# CLK_INPUT.net
KiCad netlist of a schematic drawn in Altium Designer
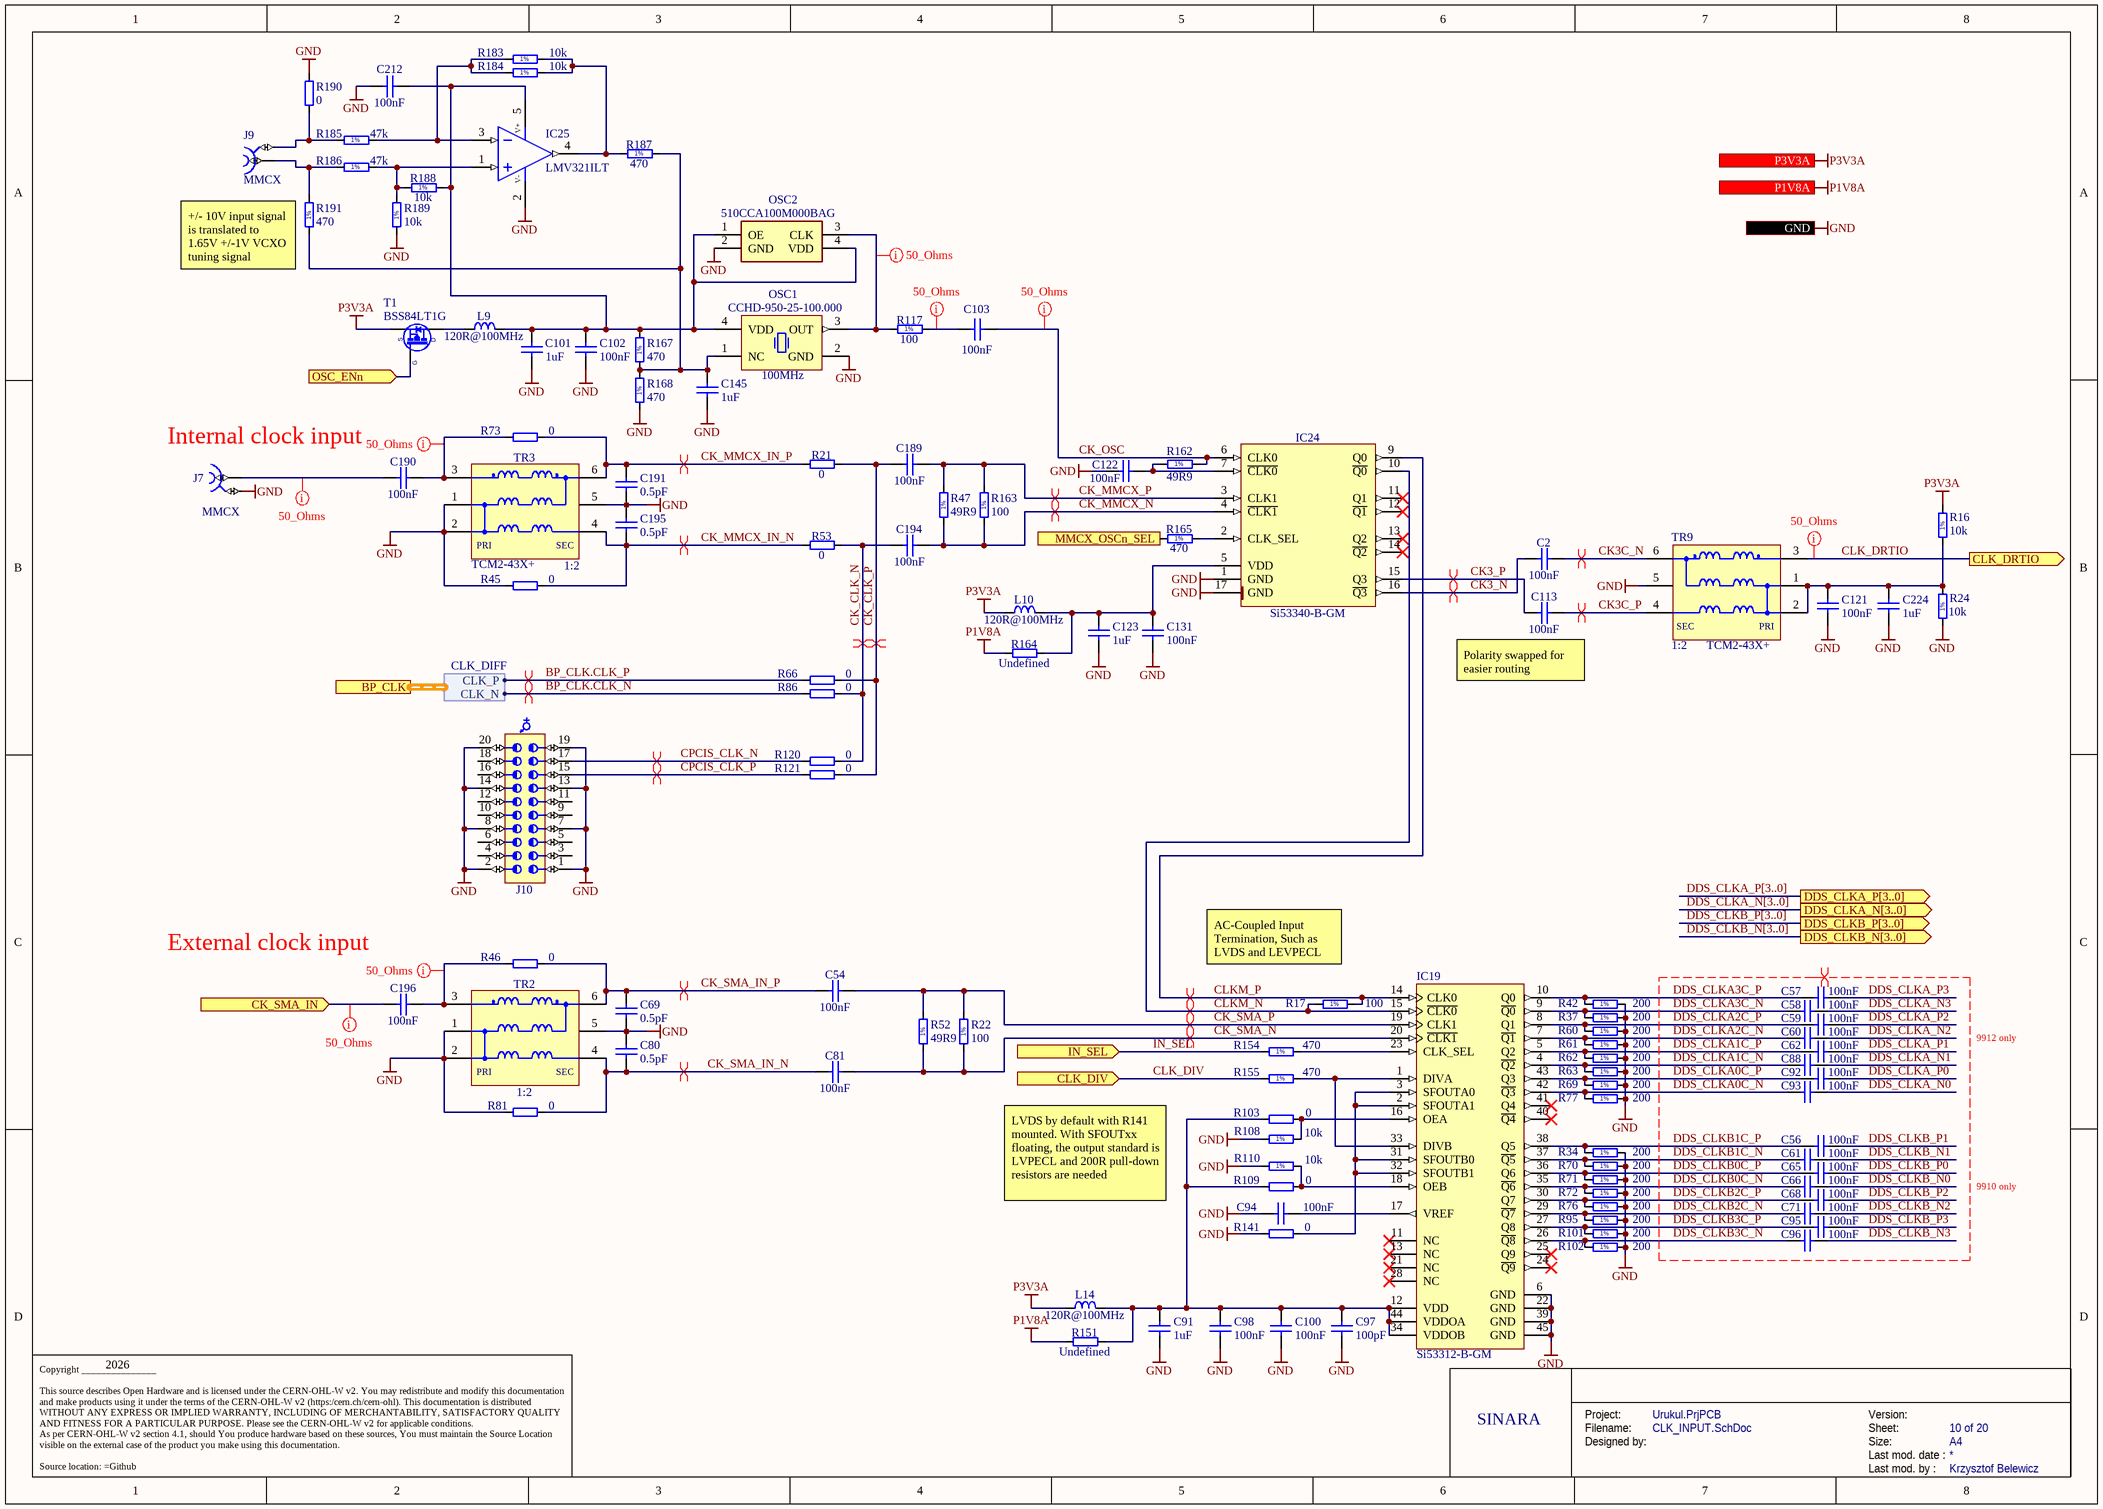
[diagram p0: CLK_INPUT.SchDoc]

(export (version "E")
  (design (tool "Eeschema 10.0.6"))
  (components
    (comp (ref "C2")
      (value "100nF")
      (footprint "CAPC1005X55N")
      (description "Non-polarised capacitor")
      (fields
        (field (name "PART NUMBER") "CC0402_100NF_16V_10%_X5R")
        (field (name "VOLTAGE") "16V")
        (field (name "AUTHOR") "CERN DEM JLC")
      )
      (libsource (lib "Capacitors") (part "Capacitor - non polarized"))
    )
    (comp (ref "C54")
      (value "100nF")
      (footprint "CAPC1005X55N")
      (description "Non-polarised capacitor")
      (fields
        (field (name "PART NUMBER") "CC0402_100NF_16V_10%_X5R")
        (field (name "VOLTAGE") "16V")
        (field (name "AUTHOR") "CERN DEM JLC")
      )
      (libsource (lib "Capacitors") (part "Capacitor - non polarized"))
    )
    (comp (ref "C56")
      (value "100nF")
      (footprint "CAPC1005X55N")
      (description "Non-polarised capacitor")
      (fields
        (field (name "PART NUMBER") "CC0402_100NF_16V_10%_X5R")
        (field (name "VOLTAGE") "16V")
        (field (name "AUTHOR") "CERN DEM JLC")
      )
      (libsource (lib "Capacitors") (part "Capacitor - non polarized"))
    )
    (comp (ref "C57")
      (value "100nF")
      (footprint "CAPC1005X55N")
      (description "Non-polarised capacitor")
      (fields
        (field (name "PART NUMBER") "CC0402_100NF_16V_10%_X5R")
        (field (name "VOLTAGE") "16V")
        (field (name "AUTHOR") "CERN DEM JLC")
      )
      (libsource (lib "Capacitors") (part "Capacitor - non polarized"))
    )
    (comp (ref "C58")
      (value "100nF")
      (footprint "CAPC1005X55N")
      (description "Non-polarised capacitor")
      (fields
        (field (name "PART NUMBER") "CC0402_100NF_16V_10%_X5R")
        (field (name "VOLTAGE") "16V")
        (field (name "AUTHOR") "CERN DEM JLC")
      )
      (libsource (lib "Capacitors") (part "Capacitor - non polarized"))
    )
    (comp (ref "C59")
      (value "100nF")
      (footprint "CAPC1005X55N")
      (description "Non-polarised capacitor")
      (fields
        (field (name "PART NUMBER") "CC0402_100NF_16V_10%_X5R")
        (field (name "VOLTAGE") "16V")
        (field (name "AUTHOR") "CERN DEM JLC")
      )
      (libsource (lib "Capacitors") (part "Capacitor - non polarized"))
    )
    (comp (ref "C60")
      (value "100nF")
      (footprint "CAPC1005X55N")
      (description "Non-polarised capacitor")
      (fields
        (field (name "PART NUMBER") "CC0402_100NF_16V_10%_X5R")
        (field (name "VOLTAGE") "16V")
        (field (name "AUTHOR") "CERN DEM JLC")
      )
      (libsource (lib "Capacitors") (part "Capacitor - non polarized"))
    )
    (comp (ref "C61")
      (value "100nF")
      (footprint "CAPC1005X55N")
      (description "Non-polarised capacitor")
      (fields
        (field (name "PART NUMBER") "CC0402_100NF_16V_10%_X5R")
        (field (name "VOLTAGE") "16V")
        (field (name "AUTHOR") "CERN DEM JLC")
      )
      (libsource (lib "Capacitors") (part "Capacitor - non polarized"))
    )
    (comp (ref "C62")
      (value "100nF")
      (footprint "CAPC1005X55N")
      (description "Non-polarised capacitor")
      (fields
        (field (name "PART NUMBER") "CC0402_100NF_16V_10%_X5R")
        (field (name "VOLTAGE") "16V")
        (field (name "AUTHOR") "CERN DEM JLC")
      )
      (libsource (lib "Capacitors") (part "Capacitor - non polarized"))
    )
    (comp (ref "C65")
      (value "100nF")
      (footprint "CAPC1005X55N")
      (description "Non-polarised capacitor")
      (fields
        (field (name "PART NUMBER") "CC0402_100NF_16V_10%_X5R")
        (field (name "VOLTAGE") "16V")
        (field (name "AUTHOR") "CERN DEM JLC")
      )
      (libsource (lib "Capacitors") (part "Capacitor - non polarized"))
    )
    (comp (ref "C66")
      (value "100nF")
      (footprint "CAPC1005X55N")
      (description "Non-polarised capacitor")
      (fields
        (field (name "PART NUMBER") "CC0402_100NF_16V_10%_X5R")
        (field (name "VOLTAGE") "16V")
        (field (name "AUTHOR") "CERN DEM JLC")
      )
      (libsource (lib "Capacitors") (part "Capacitor - non polarized"))
    )
    (comp (ref "C68")
      (value "100nF")
      (footprint "CAPC1005X55N")
      (description "Non-polarised capacitor")
      (fields
        (field (name "PART NUMBER") "CC0402_100NF_16V_10%_X5R")
        (field (name "VOLTAGE") "16V")
        (field (name "AUTHOR") "CERN DEM JLC")
      )
      (libsource (lib "Capacitors") (part "Capacitor - non polarized"))
    )
    (comp (ref "C69")
      (value "0.5pF")
      (footprint "CAPC1005X50N")
      (description "Non-polarised capacitor")
      (fields
        (field (name "PART NUMBER") "CC0402_0.5PF_25V_0.05PF_AVX_04023J0R5ABSTR")
        (field (name "VOLTAGE") "25V")
        (field (name "AUTHOR") "CERN DEM JLC")
      )
      (libsource (lib "Capacitors") (part "Capacitor - non polarized"))
    )
    (comp (ref "C71")
      (value "100nF")
      (footprint "CAPC1005X55N")
      (description "Non-polarised capacitor")
      (fields
        (field (name "PART NUMBER") "CC0402_100NF_16V_10%_X5R")
        (field (name "VOLTAGE") "16V")
        (field (name "AUTHOR") "CERN DEM JLC")
      )
      (libsource (lib "Capacitors") (part "Capacitor - non polarized"))
    )
    (comp (ref "C80")
      (value "0.5pF")
      (footprint "CAPC1005X50N")
      (description "Non-polarised capacitor")
      (fields
        (field (name "PART NUMBER") "CC0402_0.5PF_25V_0.05PF_AVX_04023J0R5ABSTR")
        (field (name "VOLTAGE") "25V")
        (field (name "AUTHOR") "CERN DEM JLC")
      )
      (libsource (lib "Capacitors") (part "Capacitor - non polarized"))
    )
    (comp (ref "C81")
      (value "100nF")
      (footprint "CAPC1005X55N")
      (description "Non-polarised capacitor")
      (fields
        (field (name "PART NUMBER") "CC0402_100NF_16V_10%_X5R")
        (field (name "VOLTAGE") "16V")
        (field (name "AUTHOR") "CERN DEM JLC")
      )
      (libsource (lib "Capacitors") (part "Capacitor - non polarized"))
    )
    (comp (ref "C88")
      (value "100nF")
      (footprint "CAPC1005X55N")
      (description "Non-polarised capacitor")
      (fields
        (field (name "PART NUMBER") "CC0402_100NF_16V_10%_X5R")
        (field (name "VOLTAGE") "16V")
        (field (name "AUTHOR") "CERN DEM JLC")
      )
      (libsource (lib "Capacitors") (part "Capacitor - non polarized"))
    )
    (comp (ref "C91")
      (value "1uF")
      (footprint "CAPC1005X55N")
      (description "Non-polarised capacitor")
      (fields
        (field (name "PART NUMBER") "CC0402_1UF_16V_10%_X5R")
        (field (name "VOLTAGE") "16V")
        (field (name "AUTHOR") "CERN DEM JLC")
      )
      (libsource (lib "Capacitors") (part "Capacitor - non polarized"))
    )
    (comp (ref "C92")
      (value "100nF")
      (footprint "CAPC1005X55N")
      (description "Non-polarised capacitor")
      (fields
        (field (name "PART NUMBER") "CC0402_100NF_16V_10%_X5R")
        (field (name "VOLTAGE") "16V")
        (field (name "AUTHOR") "CERN DEM JLC")
      )
      (libsource (lib "Capacitors") (part "Capacitor - non polarized"))
    )
    (comp (ref "C93")
      (value "100nF")
      (footprint "CAPC1005X55N")
      (description "Non-polarised capacitor")
      (fields
        (field (name "PART NUMBER") "CC0402_100NF_16V_10%_X5R")
        (field (name "VOLTAGE") "16V")
        (field (name "AUTHOR") "CERN DEM JLC")
      )
      (libsource (lib "Capacitors") (part "Capacitor - non polarized"))
    )
    (comp (ref "C94")
      (value "100nF")
      (footprint "CAPC1005X55N")
      (description "Non-polarised capacitor")
      (fields
        (field (name "PART NUMBER") "CC0402_100NF_16V_10%_X5R")
        (field (name "VOLTAGE") "16V")
        (field (name "AUTHOR") "CERN DEM JLC")
      )
      (libsource (lib "Capacitors") (part "Capacitor - non polarized"))
    )
    (comp (ref "C95")
      (value "100nF")
      (footprint "CAPC1005X55N")
      (description "Non-polarised capacitor")
      (fields
        (field (name "PART NUMBER") "CC0402_100NF_16V_10%_X5R")
        (field (name "VOLTAGE") "16V")
        (field (name "AUTHOR") "CERN DEM JLC")
      )
      (libsource (lib "Capacitors") (part "Capacitor - non polarized"))
    )
    (comp (ref "C96")
      (value "100nF")
      (footprint "CAPC1005X55N")
      (description "Non-polarised capacitor")
      (fields
        (field (name "PART NUMBER") "CC0402_100NF_16V_10%_X5R")
        (field (name "VOLTAGE") "16V")
        (field (name "AUTHOR") "CERN DEM JLC")
      )
      (libsource (lib "Capacitors") (part "Capacitor - non polarized"))
    )
    (comp (ref "C97")
      (value "100pF")
      (footprint "CAPC1005X55N")
      (description "Non-polarised capacitor")
      (fields
        (field (name "PART NUMBER") "CC0402_100PF_50V_5%_C0G")
        (field (name "VOLTAGE") "50V")
        (field (name "AUTHOR") "CERN DEM JLC")
      )
      (libsource (lib "Capacitors") (part "Capacitor - non polarized"))
    )
    (comp (ref "C98")
      (value "100nF")
      (footprint "CAPC1005X55N")
      (description "Non-polarised capacitor")
      (fields
        (field (name "PART NUMBER") "CC0402_100NF_16V_10%_X5R")
        (field (name "VOLTAGE") "16V")
        (field (name "AUTHOR") "CERN DEM JLC")
      )
      (libsource (lib "Capacitors") (part "Capacitor - non polarized"))
    )
    (comp (ref "C100")
      (value "100nF")
      (footprint "CAPC1005X55N")
      (description "Non-polarised capacitor")
      (fields
        (field (name "PART NUMBER") "CC0402_100NF_16V_10%_X5R")
        (field (name "VOLTAGE") "16V")
        (field (name "AUTHOR") "CERN DEM JLC")
      )
      (libsource (lib "Capacitors") (part "Capacitor - non polarized"))
    )
    (comp (ref "C101")
      (value "1uF")
      (footprint "CAPC1005X55N")
      (description "Non-polarised capacitor")
      (fields
        (field (name "PART NUMBER") "CC0402_1UF_16V_10%_X5R")
        (field (name "VOLTAGE") "16V")
        (field (name "AUTHOR") "CERN DEM JLC")
      )
      (libsource (lib "Capacitors") (part "Capacitor - non polarized"))
    )
    (comp (ref "C102")
      (value "100nF")
      (footprint "CAPC1005X55N")
      (description "Non-polarised capacitor")
      (fields
        (field (name "PART NUMBER") "CC0402_100NF_16V_10%_X5R")
        (field (name "VOLTAGE") "16V")
        (field (name "AUTHOR") "CERN DEM JLC")
      )
      (libsource (lib "Capacitors") (part "Capacitor - non polarized"))
    )
    (comp (ref "C103")
      (value "100nF")
      (footprint "CAPC1005X55N")
      (description "Non-polarised capacitor")
      (fields
        (field (name "PART NUMBER") "CC0402_100NF_16V_10%_X5R")
        (field (name "VOLTAGE") "16V")
        (field (name "AUTHOR") "CERN DEM JLC")
      )
      (libsource (lib "Capacitors") (part "Capacitor - non polarized"))
    )
    (comp (ref "C113")
      (value "100nF")
      (footprint "CAPC1005X55N")
      (description "Non-polarised capacitor")
      (fields
        (field (name "PART NUMBER") "CC0402_100NF_16V_10%_X5R")
        (field (name "VOLTAGE") "16V")
        (field (name "AUTHOR") "CERN DEM JLC")
      )
      (libsource (lib "Capacitors") (part "Capacitor - non polarized"))
    )
    (comp (ref "C121")
      (value "100nF")
      (footprint "CAPC1005X55N")
      (description "Non-polarised capacitor")
      (fields
        (field (name "PART NUMBER") "CC0402_100NF_16V_10%_X5R")
        (field (name "VOLTAGE") "16V")
        (field (name "AUTHOR") "CERN DEM JLC")
      )
      (libsource (lib "Capacitors") (part "Capacitor - non polarized"))
    )
    (comp (ref "C122")
      (value "100nF")
      (footprint "CAPC1005X55N")
      (description "Non-polarised capacitor")
      (fields
        (field (name "PART NUMBER") "CC0402_100NF_16V_10%_X5R")
        (field (name "VOLTAGE") "16V")
        (field (name "AUTHOR") "CERN DEM JLC")
      )
      (libsource (lib "Capacitors") (part "Capacitor - non polarized"))
    )
    (comp (ref "C123")
      (value "1uF")
      (footprint "CAPC1005X55N")
      (description "Non-polarised capacitor")
      (fields
        (field (name "PART NUMBER") "CC0402_1UF_16V_10%_X5R")
        (field (name "VOLTAGE") "16V")
        (field (name "AUTHOR") "CERN DEM JLC")
      )
      (libsource (lib "Capacitors") (part "Capacitor - non polarized"))
    )
    (comp (ref "C131")
      (value "100nF")
      (footprint "CAPC1005X55N")
      (description "Non-polarised capacitor")
      (fields
        (field (name "PART NUMBER") "CC0402_100NF_16V_10%_X5R")
        (field (name "VOLTAGE") "16V")
        (field (name "AUTHOR") "CERN DEM JLC")
      )
      (libsource (lib "Capacitors") (part "Capacitor - non polarized"))
    )
    (comp (ref "C145")
      (value "1uF")
      (footprint "CAPC1005X55N")
      (description "Non-polarised capacitor")
      (fields
        (field (name "PART NUMBER") "CC0402_1UF_16V_10%_X5R")
        (field (name "VOLTAGE") "16V")
        (field (name "AUTHOR") "CERN DEM JLC")
      )
      (libsource (lib "Capacitors") (part "Capacitor - non polarized"))
    )
    (comp (ref "C189")
      (value "100nF")
      (footprint "CAPC1005X55N")
      (description "Non-polarised capacitor")
      (fields
        (field (name "PART NUMBER") "CC0402_100NF_16V_10%_X5R")
        (field (name "VOLTAGE") "16V")
        (field (name "AUTHOR") "CERN DEM JLC")
      )
      (libsource (lib "Capacitors") (part "Capacitor - non polarized"))
    )
    (comp (ref "C190")
      (value "100nF")
      (footprint "CAPC1005X55N")
      (description "Non-polarised capacitor")
      (fields
        (field (name "PART NUMBER") "CC0402_100NF_16V_10%_X5R")
        (field (name "VOLTAGE") "16V")
        (field (name "AUTHOR") "CERN DEM JLC")
      )
      (libsource (lib "Capacitors") (part "Capacitor - non polarized"))
    )
    (comp (ref "C191")
      (value "0.5pF")
      (footprint "CAPC1005X50N")
      (description "Non-polarised capacitor")
      (fields
        (field (name "PART NUMBER") "CC0402_0.5PF_25V_0.05PF_AVX_04023J0R5ABSTR")
        (field (name "VOLTAGE") "25V")
        (field (name "AUTHOR") "CERN DEM JLC")
      )
      (libsource (lib "Capacitors") (part "Capacitor - non polarized"))
    )
    (comp (ref "C194")
      (value "100nF")
      (footprint "CAPC1005X55N")
      (description "Non-polarised capacitor")
      (fields
        (field (name "PART NUMBER") "CC0402_100NF_16V_10%_X5R")
        (field (name "VOLTAGE") "16V")
        (field (name "AUTHOR") "CERN DEM JLC")
      )
      (libsource (lib "Capacitors") (part "Capacitor - non polarized"))
    )
    (comp (ref "C195")
      (value "0.5pF")
      (footprint "CAPC1005X50N")
      (description "Non-polarised capacitor")
      (fields
        (field (name "PART NUMBER") "CC0402_0.5PF_25V_0.05PF_AVX_04023J0R5ABSTR")
        (field (name "VOLTAGE") "25V")
        (field (name "AUTHOR") "CERN DEM JLC")
      )
      (libsource (lib "Capacitors") (part "Capacitor - non polarized"))
    )
    (comp (ref "C196")
      (value "100nF")
      (footprint "CAPC1005X55N")
      (description "Non-polarised capacitor")
      (fields
        (field (name "PART NUMBER") "CC0402_100NF_16V_10%_X5R")
        (field (name "VOLTAGE") "16V")
        (field (name "AUTHOR") "CERN DEM JLC")
      )
      (libsource (lib "Capacitors") (part "Capacitor - non polarized"))
    )
    (comp (ref "C212")
      (value "100nF")
      (footprint "CAPC1005X55N")
      (description "Non-polarised capacitor")
      (fields
        (field (name "PART NUMBER") "CC0402_100NF_16V_10%_X5R")
        (field (name "VOLTAGE") "16V")
        (field (name "AUTHOR") "CERN DEM JLC")
      )
      (libsource (lib "Capacitors") (part "Capacitor - non polarized"))
    )
    (comp (ref "C224")
      (value "1uF")
      (footprint "CAPC1005X55N")
      (description "Non-polarised capacitor")
      (fields
        (field (name "PART NUMBER") "CC0402_1UF_16V_10%_X5R")
        (field (name "VOLTAGE") "16V")
        (field (name "AUTHOR") "CERN DEM JLC")
      )
      (libsource (lib "Capacitors") (part "Capacitor - non polarized"))
    )
    (comp (ref "IC19")
      (value "Si53312-B-GM")
      (footprint "SLAB-QFN-44-2800x2800TP_N")
      (fields (field (name "MANUFACTURER") "Silicon Labs"))
      (libsource (lib "Altium Content Vault") (part "SLAB-Si53312-QFN-44-45"))
    )
    (comp (ref "IC24")
      (value "Si53340-B-GM")
      (footprint "QFN50P300X300X90-17N-S175")
      (description "Low-Jitter LVDS Fanout Clock Buffers, 10-Output,  Any-Input, Any-Frequency up to 1250MHz")
      (fields (field (name "MANUFACTURER") "SILICON LABS") (field (name "AUTHOR") "CERN DEM MR"))
      (libsource (lib "ICs And Semiconductors") (part "Si53340"))
    )
    (comp (ref "IC25")
      (value "LMV321ILT")
      (footprint "SOT95P280X145-5N")
      (description "Operational Amplifier")
      (fields (field (name "MANUFACTURER") "ST MICROELECTRONICS") (field (name "AUTHOR") "CERN DEM MR"))
      (libsource (lib "ICs And Semiconductors") (part "Operational Amplifier Type10"))
    )
    (comp (ref "J7")
      (value "MMCX")
      (footprint "SAMTEC_MMCX-J-P-H-ST-TH1")
      (fields
        (field (name "PART NUMBER") "SAMTEC_MMCX-J-P-H-ST-TH1")
        (field (name "MANUFACTURER") "SAMTEC")
        (field (name "MANUFACTURER PART NUMBER") "MMCX-J-P-H-ST-TH1")
        (field (name "AUTHOR") "CERN DEM JLC")
      )
      (libsource (lib "Connectors") (part "Coax_1Female_1Shield"))
    )
    (comp (ref "J9")
      (value "MMCX")
      (footprint "SAMTEC_MMCX-J-P-H-ST-TH1")
      (fields
        (field (name "PART NUMBER") "SAMTEC_MMCX-J-P-H-ST-TH1")
        (field (name "MANUFACTURER") "SAMTEC")
        (field (name "MANUFACTURER PART NUMBER") "MMCX-J-P-H-ST-TH1")
        (field (name "AUTHOR") "CERN DEM JLC")
      )
      (libsource (lib "") (part "Coax_1Female_1Shield_1"))
    )
    (comp (ref "J10")
      (value "~")
      (footprint "SAMTEC_LSS-110-01-L-DV-A")
      (description "Connector 20 Hermaphroditic")
      (fields
        (field (name "PART NUMBER") "SAMTEC_LSS-110-01-L-DV-A")
        (field (name "MANUFACTURER") "SAMTEC")
        (field (name "AUTHOR") "CERN DEM MR")
      )
      (libsource (lib "Connectors") (part "Connector 20 Hermaphroditic"))
    )
    (comp (ref "L9")
      (value "120R@100MHz")
      (footprint "INDC1608X95N")
      (description "Inductor")
      (fields
        (field (name "PART NUMBER") "IND0603_MURATA_BLM18PG121SN1D")
        (field (name "POWER") "2A")
        (field (name "AUTHOR") "CERN DEM BC")
      )
      (libsource (lib "Inductors & Transformers") (part "Inductor"))
    )
    (comp (ref "L10")
      (value "120R@100MHz")
      (footprint "INDC1608X95N")
      (description "Inductor")
      (fields
        (field (name "PART NUMBER") "IND0603_MURATA_BLM18PG121SN1D")
        (field (name "POWER") "2A")
        (field (name "AUTHOR") "CERN DEM BC")
      )
      (libsource (lib "Inductors & Transformers") (part "Inductor"))
    )
    (comp (ref "L14")
      (value "120R@100MHz")
      (footprint "INDC1608X95N")
      (description "Inductor")
      (fields
        (field (name "PART NUMBER") "IND0603_MURATA_BLM18PG121SN1D")
        (field (name "POWER") "2A")
        (field (name "AUTHOR") "CERN DEM BC")
      )
      (libsource (lib "Inductors & Transformers") (part "Inductor"))
    )
    (comp (ref "OSC1")
      (value "100MHz")
      (footprint "OSC_CRYSTEK_CCHD-950")
      (description "100MHz low noise oscillator")
      (fields
        (field (name "PART NUMBER") "OSC_100MHZ_CRYSTEK_CCHD-950-25-100.000")
        (field (name "MANUFACTURER") "CRYSTEK CRYSTAL")
        (field (name "MANUFACTURER PART NUMBER") "CCHD-950-25-100.000")
        (field (name "AUTHOR") "GK")
      )
      (libsource (lib "LIBRARY_SCH") (part "OSC_CCHD-950"))
    )
    (comp (ref "OSC2")
      (value "510CCA100M000BAG")
      (footprint "SamacSys:510CBA49M1520BAG")
      (description "Crystal or Oscillator")
      (fields (field (name "MOUSER PART NUMBER") "634-510CCA100M000BAG"))
      (libsource (lib "*") (part "510CCA100M000BAG"))
    )
    (comp (ref "R16")
      (value "10k")
      (footprint "RESC1005X40N")
      (description "Resistor - 1%")
      (fields
        (field (name "PART NUMBER") "R0402_10K_1%_0.0625W_100PPM")
        (field (name "POWER") "0.0625W")
        (field (name "AUTHOR") "CERN DEM JLC")
      )
      (libsource (lib "Resistors") (part "Resistor - 1%"))
    )
    (comp (ref "R17")
      (value "100")
      (footprint "RESC1005X40N")
      (description "Resistor - 1%")
      (fields
        (field (name "PART NUMBER") "R0402_100R_1%_0.0625W_100PPM")
        (field (name "POWER") "0.0625W")
        (field (name "AUTHOR") "CERN DEM JLC")
      )
      (libsource (lib "Resistors") (part "Resistor - 1%"))
    )
    (comp (ref "R21")
      (value "0")
      (footprint "RESC1005X40N")
      (description "Resistor")
      (fields
        (field (name "PART NUMBER") "R0402_0R_JUMPER")
        (field (name "MANUFACTURER") "GENERIC")
        (field (name "AUTHOR") "CERN DEM JLC")
      )
      (libsource (lib "Resistors") (part "Resistor"))
    )
    (comp (ref "R22")
      (value "100")
      (footprint "RESC1005X40N")
      (description "Resistor - 1%")
      (fields
        (field (name "PART NUMBER") "R0402_100R_1%_0.0625W_100PPM")
        (field (name "POWER") "0.0625W")
        (field (name "AUTHOR") "CERN DEM JLC")
      )
      (libsource (lib "Resistors") (part "Resistor - 1%"))
    )
    (comp (ref "R24")
      (value "10k")
      (footprint "RESC1005X40N")
      (description "Resistor - 1%")
      (fields
        (field (name "PART NUMBER") "R0402_10K_1%_0.0625W_100PPM")
        (field (name "POWER") "0.0625W")
        (field (name "AUTHOR") "CERN DEM JLC")
      )
      (libsource (lib "Resistors") (part "Resistor - 1%"))
    )
    (comp (ref "R34")
      (value "200")
      (footprint "RESC1005X40N")
      (description "Resistor - 1%")
      (fields
        (field (name "PART NUMBER") "R0402_200R_1%_0.0625W_100PPM")
        (field (name "POWER") "0.0625W")
        (field (name "AUTHOR") "CERN DEM JLC")
      )
      (libsource (lib "Resistors") (part "Resistor - 1%"))
    )
    (comp (ref "R37")
      (value "200")
      (footprint "RESC1005X40N")
      (description "Resistor - 1%")
      (fields
        (field (name "PART NUMBER") "R0402_200R_1%_0.0625W_100PPM")
        (field (name "POWER") "0.0625W")
        (field (name "AUTHOR") "CERN DEM JLC")
      )
      (libsource (lib "Resistors") (part "Resistor - 1%"))
    )
    (comp (ref "R42")
      (value "200")
      (footprint "RESC1005X40N")
      (description "Resistor - 1%")
      (fields
        (field (name "PART NUMBER") "R0402_200R_1%_0.0625W_100PPM")
        (field (name "POWER") "0.0625W")
        (field (name "AUTHOR") "CERN DEM JLC")
      )
      (libsource (lib "Resistors") (part "Resistor - 1%"))
    )
    (comp (ref "R45")
      (value "0")
      (footprint "RESC1005X40N")
      (description "Resistor")
      (fields
        (field (name "PART NUMBER") "R0402_0R_JUMPER")
        (field (name "MANUFACTURER") "GENERIC")
        (field (name "AUTHOR") "CERN DEM JLC")
      )
      (libsource (lib "Resistors") (part "Resistor"))
    )
    (comp (ref "R46")
      (value "0")
      (footprint "RESC1005X40N")
      (description "Resistor")
      (fields
        (field (name "PART NUMBER") "R0402_0R_JUMPER")
        (field (name "MANUFACTURER") "GENERIC")
        (field (name "AUTHOR") "CERN DEM JLC")
      )
      (libsource (lib "Resistors") (part "Resistor"))
    )
    (comp (ref "R47")
      (value "49R9")
      (footprint "RESC1005X40N")
      (description "Resistor - 1%")
      (fields
        (field (name "PART NUMBER") "R0402_49R9_1%_0.0625W_100PPM")
        (field (name "POWER") "0.0625W")
        (field (name "AUTHOR") "CERN DEM JLC")
      )
      (libsource (lib "Resistors") (part "Resistor - 1%"))
    )
    (comp (ref "R52")
      (value "49R9")
      (footprint "RESC1005X40N")
      (description "Resistor - 1%")
      (fields
        (field (name "PART NUMBER") "R0402_49R9_1%_0.0625W_100PPM")
        (field (name "POWER") "0.0625W")
        (field (name "AUTHOR") "CERN DEM JLC")
      )
      (libsource (lib "Resistors") (part "Resistor - 1%"))
    )
    (comp (ref "R53")
      (value "0")
      (footprint "RESC1005X40N")
      (description "Resistor")
      (fields
        (field (name "PART NUMBER") "R0402_0R_JUMPER")
        (field (name "MANUFACTURER") "GENERIC")
        (field (name "AUTHOR") "CERN DEM JLC")
      )
      (libsource (lib "Resistors") (part "Resistor"))
    )
    (comp (ref "R60")
      (value "200")
      (footprint "RESC1005X40N")
      (description "Resistor - 1%")
      (fields
        (field (name "PART NUMBER") "R0402_200R_1%_0.0625W_100PPM")
        (field (name "POWER") "0.0625W")
        (field (name "AUTHOR") "CERN DEM JLC")
      )
      (libsource (lib "Resistors") (part "Resistor - 1%"))
    )
    (comp (ref "R61")
      (value "200")
      (footprint "RESC1005X40N")
      (description "Resistor - 1%")
      (fields
        (field (name "PART NUMBER") "R0402_200R_1%_0.0625W_100PPM")
        (field (name "POWER") "0.0625W")
        (field (name "AUTHOR") "CERN DEM JLC")
      )
      (libsource (lib "Resistors") (part "Resistor - 1%"))
    )
    (comp (ref "R62")
      (value "200")
      (footprint "RESC1005X40N")
      (description "Resistor - 1%")
      (fields
        (field (name "PART NUMBER") "R0402_200R_1%_0.0625W_100PPM")
        (field (name "POWER") "0.0625W")
        (field (name "AUTHOR") "CERN DEM JLC")
      )
      (libsource (lib "Resistors") (part "Resistor - 1%"))
    )
    (comp (ref "R63")
      (value "200")
      (footprint "RESC1005X40N")
      (description "Resistor - 1%")
      (fields
        (field (name "PART NUMBER") "R0402_200R_1%_0.0625W_100PPM")
        (field (name "POWER") "0.0625W")
        (field (name "AUTHOR") "CERN DEM JLC")
      )
      (libsource (lib "Resistors") (part "Resistor - 1%"))
    )
    (comp (ref "R66")
      (value "0")
      (footprint "RESC1005X40N")
      (description "Resistor")
      (fields
        (field (name "PART NUMBER") "R0402_0R_JUMPER")
        (field (name "MANUFACTURER") "GENERIC")
        (field (name "AUTHOR") "CERN DEM JLC")
      )
      (libsource (lib "Resistors") (part "Resistor"))
    )
    (comp (ref "R69")
      (value "200")
      (footprint "RESC1005X40N")
      (description "Resistor - 1%")
      (fields
        (field (name "PART NUMBER") "R0402_200R_1%_0.0625W_100PPM")
        (field (name "POWER") "0.0625W")
        (field (name "AUTHOR") "CERN DEM JLC")
      )
      (libsource (lib "Resistors") (part "Resistor - 1%"))
    )
    (comp (ref "R70")
      (value "200")
      (footprint "RESC1005X40N")
      (description "Resistor - 1%")
      (fields
        (field (name "PART NUMBER") "R0402_200R_1%_0.0625W_100PPM")
        (field (name "POWER") "0.0625W")
        (field (name "AUTHOR") "CERN DEM JLC")
      )
      (libsource (lib "Resistors") (part "Resistor - 1%"))
    )
    (comp (ref "R71")
      (value "200")
      (footprint "RESC1005X40N")
      (description "Resistor - 1%")
      (fields
        (field (name "PART NUMBER") "R0402_200R_1%_0.0625W_100PPM")
        (field (name "POWER") "0.0625W")
        (field (name "AUTHOR") "CERN DEM JLC")
      )
      (libsource (lib "Resistors") (part "Resistor - 1%"))
    )
    (comp (ref "R72")
      (value "200")
      (footprint "RESC1005X40N")
      (description "Resistor - 1%")
      (fields
        (field (name "PART NUMBER") "R0402_200R_1%_0.0625W_100PPM")
        (field (name "POWER") "0.0625W")
        (field (name "AUTHOR") "CERN DEM JLC")
      )
      (libsource (lib "Resistors") (part "Resistor - 1%"))
    )
    (comp (ref "R73")
      (value "0")
      (footprint "RESC1005X40N")
      (description "Resistor")
      (fields
        (field (name "PART NUMBER") "R0402_0R_JUMPER")
        (field (name "MANUFACTURER") "GENERIC")
        (field (name "AUTHOR") "CERN DEM JLC")
      )
      (libsource (lib "Resistors") (part "Resistor"))
    )
    (comp (ref "R76")
      (value "200")
      (footprint "RESC1005X40N")
      (description "Resistor - 1%")
      (fields
        (field (name "PART NUMBER") "R0402_200R_1%_0.0625W_100PPM")
        (field (name "POWER") "0.0625W")
        (field (name "AUTHOR") "CERN DEM JLC")
      )
      (libsource (lib "Resistors") (part "Resistor - 1%"))
    )
    (comp (ref "R77")
      (value "200")
      (footprint "RESC1005X40N")
      (description "Resistor - 1%")
      (fields
        (field (name "PART NUMBER") "R0402_200R_1%_0.0625W_100PPM")
        (field (name "POWER") "0.0625W")
        (field (name "AUTHOR") "CERN DEM JLC")
      )
      (libsource (lib "Resistors") (part "Resistor - 1%"))
    )
    (comp (ref "R81")
      (value "0")
      (footprint "RESC1005X40N")
      (description "Resistor")
      (fields
        (field (name "PART NUMBER") "R0402_0R_JUMPER")
        (field (name "MANUFACTURER") "GENERIC")
        (field (name "AUTHOR") "CERN DEM JLC")
      )
      (libsource (lib "Resistors") (part "Resistor"))
    )
    (comp (ref "R86")
      (value "0")
      (footprint "RESC1005X40N")
      (description "Resistor")
      (fields
        (field (name "PART NUMBER") "R0402_0R_JUMPER")
        (field (name "MANUFACTURER") "GENERIC")
        (field (name "AUTHOR") "CERN DEM JLC")
      )
      (libsource (lib "Resistors") (part "Resistor"))
    )
    (comp (ref "R95")
      (value "200")
      (footprint "RESC1005X40N")
      (description "Resistor - 1%")
      (fields
        (field (name "PART NUMBER") "R0402_200R_1%_0.0625W_100PPM")
        (field (name "POWER") "0.0625W")
        (field (name "AUTHOR") "CERN DEM JLC")
      )
      (libsource (lib "Resistors") (part "Resistor - 1%"))
    )
    (comp (ref "R101")
      (value "200")
      (footprint "RESC1005X40N")
      (description "Resistor - 1%")
      (fields
        (field (name "PART NUMBER") "R0402_200R_1%_0.0625W_100PPM")
        (field (name "POWER") "0.0625W")
        (field (name "AUTHOR") "CERN DEM JLC")
      )
      (libsource (lib "Resistors") (part "Resistor - 1%"))
    )
    (comp (ref "R102")
      (value "200")
      (footprint "RESC1005X40N")
      (description "Resistor - 1%")
      (fields
        (field (name "PART NUMBER") "R0402_200R_1%_0.0625W_100PPM")
        (field (name "POWER") "0.0625W")
        (field (name "AUTHOR") "CERN DEM JLC")
      )
      (libsource (lib "Resistors") (part "Resistor - 1%"))
    )
    (comp (ref "R103")
      (value "0")
      (footprint "RESC1608X55N")
      (description "Resistor")
      (fields
        (field (name "PART NUMBER") "R0603_0R_JUMPER")
        (field (name "MANUFACTURER") "GENERIC")
        (field (name "AUTHOR") "CERN DEM JLC")
      )
      (libsource (lib "Resistors") (part "Resistor"))
    )
    (comp (ref "R108")
      (value "10k")
      (footprint "RESC1005X40N")
      (description "Resistor - 1%")
      (fields
        (field (name "PART NUMBER") "R0402_10K_1%_0.0625W_100PPM")
        (field (name "POWER") "0.0625W")
        (field (name "AUTHOR") "CERN DEM JLC")
      )
      (libsource (lib "Resistors") (part "Resistor - 1%"))
    )
    (comp (ref "R109")
      (value "0")
      (footprint "RESC1608X55N")
      (description "Resistor")
      (fields
        (field (name "PART NUMBER") "R0603_0R_JUMPER")
        (field (name "MANUFACTURER") "GENERIC")
        (field (name "AUTHOR") "CERN DEM JLC")
      )
      (libsource (lib "Resistors") (part "Resistor"))
    )
    (comp (ref "R110")
      (value "10k")
      (footprint "RESC1005X40N")
      (description "Resistor - 1%")
      (fields
        (field (name "PART NUMBER") "R0402_10K_1%_0.0625W_100PPM")
        (field (name "POWER") "0.0625W")
        (field (name "AUTHOR") "CERN DEM JLC")
      )
      (libsource (lib "Resistors") (part "Resistor - 1%"))
    )
    (comp (ref "R117")
      (value "100")
      (footprint "RESC1005X40N")
      (description "Resistor - 1%")
      (fields
        (field (name "PART NUMBER") "R0402_100R_1%_0.0625W_100PPM")
        (field (name "POWER") "0.0625W")
        (field (name "AUTHOR") "CERN DEM JLC")
      )
      (libsource (lib "Resistors") (part "Resistor - 1%"))
    )
    (comp (ref "R120")
      (value "0")
      (footprint "RESC1005X40N")
      (description "Resistor")
      (fields
        (field (name "PART NUMBER") "R0402_0R_JUMPER")
        (field (name "MANUFACTURER") "GENERIC")
        (field (name "AUTHOR") "CERN DEM JLC")
      )
      (libsource (lib "Resistors") (part "Resistor"))
    )
    (comp (ref "R121")
      (value "0")
      (footprint "RESC1005X40N")
      (description "Resistor")
      (fields
        (field (name "PART NUMBER") "R0402_0R_JUMPER")
        (field (name "MANUFACTURER") "GENERIC")
        (field (name "AUTHOR") "CERN DEM JLC")
      )
      (libsource (lib "Resistors") (part "Resistor"))
    )
    (comp (ref "R141")
      (value "0")
      (footprint "RESC1608X55N")
      (description "Resistor")
      (fields
        (field (name "PART NUMBER") "R0603_0R_JUMPER")
        (field (name "MANUFACTURER") "GENERIC")
        (field (name "AUTHOR") "CERN DEM JLC")
      )
      (libsource (lib "Resistors") (part "Resistor"))
    )
    (comp (ref "R151")
      (value "Undefined")
      (footprint "RESC1608X55N")
      (description "Resistor")
      (fields (field (name "PART NUMBER") "R0603_NO-VALUE") (field (name "AUTHOR") "CERN DEM JLC"))
      (libsource (lib "Resistors") (part "Resistor"))
    )
    (comp (ref "R154")
      (value "470")
      (footprint "RESC1005X40N")
      (description "Resistor - 1%")
      (fields
        (field (name "PART NUMBER") "R0402_470R_1%_0.0625W_100PPM")
        (field (name "POWER") "0.0625W")
        (field (name "AUTHOR") "CERN DEM JLC")
      )
      (libsource (lib "Resistors") (part "Resistor - 1%"))
    )
    (comp (ref "R155")
      (value "470")
      (footprint "RESC1005X40N")
      (description "Resistor - 1%")
      (fields
        (field (name "PART NUMBER") "R0402_470R_1%_0.0625W_100PPM")
        (field (name "POWER") "0.0625W")
        (field (name "AUTHOR") "CERN DEM JLC")
      )
      (libsource (lib "Resistors") (part "Resistor - 1%"))
    )
    (comp (ref "R162")
      (value "49R9")
      (footprint "RESC1005X40N")
      (description "Resistor - 1%")
      (fields
        (field (name "PART NUMBER") "R0402_49R9_1%_0.0625W_100PPM")
        (field (name "POWER") "0.0625W")
        (field (name "AUTHOR") "CERN DEM JLC")
      )
      (libsource (lib "Resistors") (part "Resistor - 1%"))
    )
    (comp (ref "R163")
      (value "100")
      (footprint "RESC1005X40N")
      (description "Resistor - 1%")
      (fields
        (field (name "PART NUMBER") "R0402_100R_1%_0.0625W_100PPM")
        (field (name "POWER") "0.0625W")
        (field (name "AUTHOR") "CERN DEM JLC")
      )
      (libsource (lib "Resistors") (part "Resistor - 1%"))
    )
    (comp (ref "R164")
      (value "Undefined")
      (footprint "RESC1608X55N")
      (description "Resistor")
      (fields (field (name "PART NUMBER") "R0603_NO-VALUE") (field (name "AUTHOR") "CERN DEM JLC"))
      (libsource (lib "Resistors") (part "Resistor"))
    )
    (comp (ref "R165")
      (value "470")
      (footprint "RESC1005X40N")
      (description "Resistor - 1%")
      (fields
        (field (name "PART NUMBER") "R0402_470R_1%_0.0625W_100PPM")
        (field (name "POWER") "0.0625W")
        (field (name "AUTHOR") "CERN DEM JLC")
      )
      (libsource (lib "Resistors") (part "Resistor - 1%"))
    )
    (comp (ref "R167")
      (value "470")
      (footprint "RESC1005X40N")
      (description "Resistor - 1%")
      (fields
        (field (name "PART NUMBER") "R0402_470R_1%_0.0625W_100PPM")
        (field (name "POWER") "0.0625W")
        (field (name "AUTHOR") "CERN DEM JLC")
      )
      (libsource (lib "Resistors") (part "Resistor - 1%"))
    )
    (comp (ref "R168")
      (value "470")
      (footprint "RESC1005X40N")
      (description "Resistor - 1%")
      (fields
        (field (name "PART NUMBER") "R0402_470R_1%_0.0625W_100PPM")
        (field (name "POWER") "0.0625W")
        (field (name "AUTHOR") "CERN DEM JLC")
      )
      (libsource (lib "Resistors") (part "Resistor - 1%"))
    )
    (comp (ref "R183")
      (value "10k")
      (footprint "RESC1005X40N")
      (description "Resistor - 1%")
      (fields
        (field (name "PART NUMBER") "R0402_10K_1%_0.0625W_100PPM")
        (field (name "POWER") "0.0625W")
        (field (name "AUTHOR") "CERN DEM JLC")
      )
      (libsource (lib "Resistors") (part "Resistor - 1%"))
    )
    (comp (ref "R184")
      (value "10k")
      (footprint "RESC1005X40N")
      (description "Resistor - 1%")
      (fields
        (field (name "PART NUMBER") "R0402_10K_1%_0.0625W_100PPM")
        (field (name "POWER") "0.0625W")
        (field (name "AUTHOR") "CERN DEM JLC")
      )
      (libsource (lib "Resistors") (part "Resistor - 1%"))
    )
    (comp (ref "R185")
      (value "47k")
      (footprint "RESC1608X55N")
      (description "Resistor - 1%")
      (fields
        (field (name "PART NUMBER") "R0603_47K_1%_0.1W_100PPM")
        (field (name "POWER") "0.1W")
        (field (name "AUTHOR") "CERN DEM JLC")
      )
      (libsource (lib "Resistors") (part "Resistor - 1%"))
    )
    (comp (ref "R186")
      (value "47k")
      (footprint "RESC1608X55N")
      (description "Resistor - 1%")
      (fields
        (field (name "PART NUMBER") "R0603_47K_1%_0.1W_100PPM")
        (field (name "POWER") "0.1W")
        (field (name "AUTHOR") "CERN DEM JLC")
      )
      (libsource (lib "Resistors") (part "Resistor - 1%"))
    )
    (comp (ref "R187")
      (value "470")
      (footprint "RESC1005X40N")
      (description "Resistor - 1%")
      (fields
        (field (name "PART NUMBER") "R0402_470R_1%_0.0625W_100PPM")
        (field (name "POWER") "0.0625W")
        (field (name "AUTHOR") "CERN DEM JLC")
      )
      (libsource (lib "Resistors") (part "Resistor - 1%"))
    )
    (comp (ref "R188")
      (value "10k")
      (footprint "RESC1005X40N")
      (description "Resistor - 1%")
      (fields
        (field (name "PART NUMBER") "R0402_10K_1%_0.0625W_100PPM")
        (field (name "POWER") "0.0625W")
        (field (name "AUTHOR") "CERN DEM JLC")
      )
      (libsource (lib "Resistors") (part "Resistor - 1%"))
    )
    (comp (ref "R189")
      (value "10k")
      (footprint "RESC1005X40N")
      (description "Resistor - 1%")
      (fields
        (field (name "PART NUMBER") "R0402_10K_1%_0.0625W_100PPM")
        (field (name "POWER") "0.0625W")
        (field (name "AUTHOR") "CERN DEM JLC")
      )
      (libsource (lib "Resistors") (part "Resistor - 1%"))
    )
    (comp (ref "R190")
      (value "0")
      (footprint "RESC1005X40N")
      (description "Resistor")
      (fields
        (field (name "PART NUMBER") "R0402_0R_JUMPER")
        (field (name "MANUFACTURER") "GENERIC")
        (field (name "AUTHOR") "CERN DEM JLC")
      )
      (libsource (lib "Resistors") (part "Resistor"))
    )
    (comp (ref "R191")
      (value "470")
      (footprint "RESC1005X40N")
      (description "Resistor - 1%")
      (fields
        (field (name "PART NUMBER") "R0402_470R_1%_0.0625W_100PPM")
        (field (name "POWER") "0.0625W")
        (field (name "AUTHOR") "CERN DEM JLC")
      )
      (libsource (lib "Resistors") (part "Resistor - 1%"))
    )
    (comp (ref "T1")
      (value "BSS84LT1G")
      (footprint "SOT95P240X110-3N")
      (description "P-CHANNEL MOSFET WITH DIODE")
      (fields (field (name "MANUFACTURER") "ON SEMICONDUCTOR") (field (name "AUTHOR") "CERN DEM JLC"))
      (libsource (lib "ICs And Semiconductors") (part "P-MOSFET-D 1G 2S 3D"))
    )
    (comp (ref "TR2")
      (value "1:2")
      (footprint "XFMR_MINI-CIRCUITS_DB1627")
      (description "50 OHMS 10 to 4000 MHz RF Transformer")
      (fields
        (field (name "PART NUMBER") "XFMR_MINI-CIRCUITS_TCM2-43X+")
        (field (name "POWER") "0.4W")
        (field (name "AUTHOR") "CERN DEM BC")
      )
      (libsource (lib "Inductors & Transformers") (part "XFMR_MINI-CIRCUITS_TCM2-43X"))
    )
    (comp (ref "TR3")
      (value "1:2")
      (footprint "XFMR_MINI-CIRCUITS_DB1627")
      (description "50 OHMS 10 to 4000 MHz RF Transformer")
      (fields
        (field (name "PART NUMBER") "XFMR_MINI-CIRCUITS_TCM2-43X+")
        (field (name "POWER") "0.4W")
        (field (name "MANUFACTURER PART NUMBER") "TCM2-43X+")
        (field (name "AUTHOR") "CERN DEM BC")
      )
      (libsource (lib "Inductors & Transformers") (part "XFMR_MINI-CIRCUITS_TCM2-43X"))
    )
    (comp (ref "TR9")
      (value "1:2")
      (footprint "XFMR_MINI-CIRCUITS_DB1627")
      (description "50 OHMS 10 to 4000 MHz RF Transformer")
      (fields
        (field (name "PART NUMBER") "XFMR_MINI-CIRCUITS_TCM2-43X+")
        (field (name "POWER") "0.4W")
        (field (name "MANUFACTURER PART NUMBER") "TCM2-43X+")
        (field (name "AUTHOR") "CERN DEM BC")
      )
      (libsource (lib "") (part "XFMR_MINI-CIRCUITS_TCM2-43X_1"))
    )
  )
  (nets
    (net (code "2") (name "/BP_CLK.CLK_N") (class "Default")
      (node (ref "R86") (pin "1") (pinfunction "1_1") (pintype "passive"))
    )
    (net (code "3") (name "/BP_CLK.CLK_P") (class "Default")
      (node (ref "R66") (pin "1") (pinfunction "1_1") (pintype "passive"))
    )
    (net (code "4") (name "/CK3C_N") (class "Default")
      (node (ref "C2") (pin "2") (pinfunction "2_2") (pintype "passive"))
      (node (ref "TR9") (pin "6") (pinfunction "S1_6") (pintype "passive"))
    )
    (net (code "5") (name "/CK3C_P") (class "Default")
      (node (ref "C113") (pin "2") (pinfunction "2_2") (pintype "passive"))
      (node (ref "TR9") (pin "4") (pinfunction "S1_4") (pintype "passive"))
    )
    (net (code "6") (name "/CK3_N") (class "Default")
      (node (ref "C2") (pin "1") (pinfunction "1_1") (pintype "passive"))
      (node (ref "IC24") (pin "16") (pinfunction "~{Q3}_16") (pintype "output"))
    )
    (net (code "7") (name "/CK3_P") (class "Default")
      (node (ref "C113") (pin "1") (pinfunction "1_1") (pintype "passive"))
      (node (ref "IC24") (pin "15") (pinfunction "Q3_15") (pintype "output"))
    )
    (net (code "8") (name "/CK_CLK_N") (class "Default")
      (node (ref "C194") (pin "1") (pinfunction "1_1") (pintype "passive"))
      (node (ref "R120") (pin "2") (pinfunction "2_2") (pintype "passive"))
      (node (ref "R53") (pin "2") (pinfunction "2_2") (pintype "passive"))
      (node (ref "R86") (pin "2") (pinfunction "2_2") (pintype "passive"))
    )
    (net (code "9") (name "/CK_CLK_P") (class "Default")
      (node (ref "C189") (pin "1") (pinfunction "1_1") (pintype "passive"))
      (node (ref "R121") (pin "2") (pinfunction "2_2") (pintype "passive"))
      (node (ref "R21") (pin "2") (pinfunction "2_2") (pintype "passive"))
      (node (ref "R66") (pin "2") (pinfunction "2_2") (pintype "passive"))
    )
    (net (code "10") (name "/CK_MMCX_IN_N") (class "Default")
      (node (ref "C195") (pin "1") (pinfunction "1_1") (pintype "passive"))
      (node (ref "R45") (pin "2") (pinfunction "2_2") (pintype "passive"))
      (node (ref "R53") (pin "1") (pinfunction "1_1") (pintype "passive"))
      (node (ref "TR3") (pin "4") (pinfunction "S1_4") (pintype "passive"))
    )
    (net (code "11") (name "/CK_MMCX_IN_P") (class "Default")
      (node (ref "C191") (pin "2") (pinfunction "2_2") (pintype "passive"))
      (node (ref "R21") (pin "1") (pinfunction "1_1") (pintype "passive"))
      (node (ref "R73") (pin "2") (pinfunction "2_2") (pintype "passive"))
      (node (ref "TR3") (pin "6") (pinfunction "S1_6") (pintype "passive"))
    )
    (net (code "12") (name "/CK_MMCX_N") (class "Default")
      (node (ref "C194") (pin "2") (pinfunction "2_2") (pintype "passive"))
      (node (ref "IC24") (pin "4") (pinfunction "~{CLK1}_4") (pintype "input"))
      (node (ref "R163") (pin "2") (pinfunction "2_2") (pintype "passive"))
      (node (ref "R47") (pin "1") (pinfunction "1_1") (pintype "passive"))
    )
    (net (code "13") (name "/CK_MMCX_P") (class "Default")
      (node (ref "C189") (pin "2") (pinfunction "2_2") (pintype "passive"))
      (node (ref "IC24") (pin "3") (pinfunction "CLK1_3") (pintype "input"))
      (node (ref "R163") (pin "1") (pinfunction "1_1") (pintype "passive"))
      (node (ref "R47") (pin "2") (pinfunction "2_2") (pintype "passive"))
    )
    (net (code "14") (name "/CK_OSC") (class "Default")
      (node (ref "C103") (pin "1") (pinfunction "1_1") (pintype "passive"))
      (node (ref "IC24") (pin "6") (pinfunction "CLK0_6") (pintype "input"))
      (node (ref "R162") (pin "1") (pinfunction "1_1") (pintype "passive"))
    )
    (net (code "15") (name "/CK_SMA_IN") (class "Default")
      (node (ref "C196") (pin "1") (pinfunction "1_1") (pintype "passive"))
    )
    (net (code "16") (name "/CK_SMA_IN_N") (class "Default")
      (node (ref "C80") (pin "1") (pinfunction "1_1") (pintype "passive"))
      (node (ref "C81") (pin "1") (pinfunction "1_1") (pintype "passive"))
      (node (ref "R81") (pin "2") (pinfunction "2_2") (pintype "passive"))
      (node (ref "TR2") (pin "4") (pinfunction "S1_4") (pintype "passive"))
    )
    (net (code "17") (name "/CK_SMA_IN_P") (class "Default")
      (node (ref "C54") (pin "1") (pinfunction "1_1") (pintype "passive"))
      (node (ref "C69") (pin "2") (pinfunction "2_2") (pintype "passive"))
      (node (ref "R46") (pin "2") (pinfunction "2_2") (pintype "passive"))
      (node (ref "TR2") (pin "6") (pinfunction "S1_6") (pintype "passive"))
    )
    (net (code "18") (name "/CK_SMA_N") (class "Default")
      (node (ref "C81") (pin "2") (pinfunction "2_2") (pintype "passive"))
      (node (ref "IC19") (pin "20") (pinfunction "~{CLK1}_20") (pintype "input"))
      (node (ref "R22") (pin "2") (pinfunction "2_2") (pintype "passive"))
      (node (ref "R52") (pin "1") (pinfunction "1_1") (pintype "passive"))
    )
    (net (code "19") (name "/CK_SMA_P") (class "Default")
      (node (ref "C54") (pin "2") (pinfunction "2_2") (pintype "passive"))
      (node (ref "IC19") (pin "19") (pinfunction "CLK1_19") (pintype "input"))
      (node (ref "R22") (pin "1") (pinfunction "1_1") (pintype "passive"))
      (node (ref "R52") (pin "2") (pinfunction "2_2") (pintype "passive"))
    )
    (net (code "20") (name "/CLKM_N") (class "Default")
      (node (ref "IC19") (pin "15") (pinfunction "~{CLK0}_15") (pintype "input"))
      (node (ref "IC24") (pin "10") (pinfunction "~{Q0}_10") (pintype "output"))
      (node (ref "R17") (pin "2") (pinfunction "2_2") (pintype "passive"))
    )
    (net (code "21") (name "/CLKM_P") (class "Default")
      (node (ref "IC19") (pin "14") (pinfunction "CLK0_14") (pintype "input"))
      (node (ref "IC24") (pin "9") (pinfunction "Q0_9") (pintype "output"))
      (node (ref "R17") (pin "1") (pinfunction "1_1") (pintype "passive"))
    )
    (net (code "22") (name "/CLK_DIV") (class "Default")
      (node (ref "R155") (pin "1") (pinfunction "1_1") (pintype "passive"))
    )
    (net (code "23") (name "/CLK_DRTIO") (class "Default")
      (node (ref "TR9") (pin "3") (pinfunction "P1_3") (pintype "passive"))
    )
    (net (code "24") (name "/CPCIS_CLK_N") (class "Default")
      (node (ref "J10") (pin "17") (pinfunction "17_17") (pintype "bidirectional"))
      (node (ref "R120") (pin "1") (pinfunction "1_1") (pintype "passive"))
    )
    (net (code "25") (name "/CPCIS_CLK_P") (class "Default")
      (node (ref "J10") (pin "15") (pinfunction "15_15") (pintype "bidirectional"))
      (node (ref "R121") (pin "1") (pinfunction "1_1") (pintype "passive"))
    )
    (net (code "26") (name "/DDS_CLKA0C_N") (class "Default")
      (node (ref "C93") (pin "2") (pinfunction "2_2") (pintype "passive"))
      (node (ref "IC19") (pin "42") (pinfunction "~{Q3}_42") (pintype "output"))
      (node (ref "R77") (pin "2") (pinfunction "2_2") (pintype "passive"))
    )
    (net (code "27") (name "/DDS_CLKA0C_P") (class "Default")
      (node (ref "C92") (pin "2") (pinfunction "2_2") (pintype "passive"))
      (node (ref "IC19") (pin "43") (pinfunction "Q3_43") (pintype "output"))
      (node (ref "R69") (pin "2") (pinfunction "2_2") (pintype "passive"))
    )
    (net (code "28") (name "/DDS_CLKA1C_N") (class "Default")
      (node (ref "C88") (pin "2") (pinfunction "2_2") (pintype "passive"))
      (node (ref "IC19") (pin "4") (pinfunction "~{Q2}_4") (pintype "output"))
      (node (ref "R63") (pin "2") (pinfunction "2_2") (pintype "passive"))
    )
    (net (code "29") (name "/DDS_CLKA1C_P") (class "Default")
      (node (ref "C62") (pin "2") (pinfunction "2_2") (pintype "passive"))
      (node (ref "IC19") (pin "5") (pinfunction "Q2_5") (pintype "output"))
      (node (ref "R62") (pin "2") (pinfunction "2_2") (pintype "passive"))
    )
    (net (code "30") (name "/DDS_CLKA2C_N") (class "Default")
      (node (ref "C60") (pin "2") (pinfunction "2_2") (pintype "passive"))
      (node (ref "IC19") (pin "7") (pinfunction "~{Q1}_7") (pintype "output"))
      (node (ref "R61") (pin "2") (pinfunction "2_2") (pintype "passive"))
    )
    (net (code "31") (name "/DDS_CLKA2C_P") (class "Default")
      (node (ref "C59") (pin "2") (pinfunction "2_2") (pintype "passive"))
      (node (ref "IC19") (pin "8") (pinfunction "Q1_8") (pintype "output"))
      (node (ref "R60") (pin "2") (pinfunction "2_2") (pintype "passive"))
    )
    (net (code "32") (name "/DDS_CLKA3C_N") (class "Default")
      (node (ref "C58") (pin "2") (pinfunction "2_2") (pintype "passive"))
      (node (ref "IC19") (pin "9") (pinfunction "~{Q0}_9") (pintype "output"))
      (node (ref "R37") (pin "2") (pinfunction "2_2") (pintype "passive"))
    )
    (net (code "33") (name "/DDS_CLKA3C_P") (class "Default")
      (node (ref "C57") (pin "2") (pinfunction "2_2") (pintype "passive"))
      (node (ref "IC19") (pin "10") (pinfunction "Q0_10") (pintype "output"))
      (node (ref "R42") (pin "2") (pinfunction "2_2") (pintype "passive"))
    )
    (net (code "34") (name "/DDS_CLKA_N0") (class "Default")
      (node (ref "C93") (pin "1") (pinfunction "1_1") (pintype "passive"))
    )
    (net (code "35") (name "/DDS_CLKA_N1") (class "Default")
      (node (ref "C88") (pin "1") (pinfunction "1_1") (pintype "passive"))
    )
    (net (code "36") (name "/DDS_CLKA_N2") (class "Default")
      (node (ref "C60") (pin "1") (pinfunction "1_1") (pintype "passive"))
    )
    (net (code "37") (name "/DDS_CLKA_N3") (class "Default")
      (node (ref "C58") (pin "1") (pinfunction "1_1") (pintype "passive"))
    )
    (net (code "39") (name "/DDS_CLKA_P0") (class "Default")
      (node (ref "C92") (pin "1") (pinfunction "1_1") (pintype "passive"))
    )
    (net (code "40") (name "/DDS_CLKA_P1") (class "Default")
      (node (ref "C62") (pin "1") (pinfunction "1_1") (pintype "passive"))
    )
    (net (code "41") (name "/DDS_CLKA_P2") (class "Default")
      (node (ref "C59") (pin "1") (pinfunction "1_1") (pintype "passive"))
    )
    (net (code "42") (name "/DDS_CLKA_P3") (class "Default")
      (node (ref "C57") (pin "1") (pinfunction "1_1") (pintype "passive"))
    )
    (net (code "44") (name "/DDS_CLKB0C_N") (class "Default")
      (node (ref "C66") (pin "2") (pinfunction "2_2") (pintype "passive"))
      (node (ref "IC19") (pin "35") (pinfunction "~{Q6}_35") (pintype "output"))
      (node (ref "R72") (pin "2") (pinfunction "2_2") (pintype "passive"))
    )
    (net (code "45") (name "/DDS_CLKB0C_P") (class "Default")
      (node (ref "C65") (pin "2") (pinfunction "2_2") (pintype "passive"))
      (node (ref "IC19") (pin "36") (pinfunction "Q6_36") (pintype "output"))
      (node (ref "R71") (pin "2") (pinfunction "2_2") (pintype "passive"))
    )
    (net (code "46") (name "/DDS_CLKB1C_N") (class "Default")
      (node (ref "C61") (pin "2") (pinfunction "2_2") (pintype "passive"))
      (node (ref "IC19") (pin "37") (pinfunction "~{Q5}_37") (pintype "output"))
      (node (ref "R70") (pin "2") (pinfunction "2_2") (pintype "passive"))
    )
    (net (code "47") (name "/DDS_CLKB1C_P") (class "Default")
      (node (ref "C56") (pin "2") (pinfunction "2_2") (pintype "passive"))
      (node (ref "IC19") (pin "38") (pinfunction "Q5_38") (pintype "output"))
      (node (ref "R34") (pin "2") (pinfunction "2_2") (pintype "passive"))
    )
    (net (code "48") (name "/DDS_CLKB2C_N") (class "Default")
      (node (ref "C71") (pin "2") (pinfunction "2_2") (pintype "passive"))
      (node (ref "IC19") (pin "29") (pinfunction "~{Q7}_29") (pintype "output"))
      (node (ref "R95") (pin "2") (pinfunction "2_2") (pintype "passive"))
    )
    (net (code "49") (name "/DDS_CLKB2C_P") (class "Default")
      (node (ref "C68") (pin "2") (pinfunction "2_2") (pintype "passive"))
      (node (ref "IC19") (pin "30") (pinfunction "Q7_30") (pintype "output"))
      (node (ref "R76") (pin "2") (pinfunction "2_2") (pintype "passive"))
    )
    (net (code "50") (name "/DDS_CLKB3C_N") (class "Default")
      (node (ref "C96") (pin "2") (pinfunction "2_2") (pintype "passive"))
      (node (ref "IC19") (pin "26") (pinfunction "~{Q8}_26") (pintype "output"))
      (node (ref "R102") (pin "2") (pinfunction "2_2") (pintype "passive"))
    )
    (net (code "51") (name "/DDS_CLKB3C_P") (class "Default")
      (node (ref "C95") (pin "2") (pinfunction "2_2") (pintype "passive"))
      (node (ref "IC19") (pin "27") (pinfunction "Q8_27") (pintype "output"))
      (node (ref "R101") (pin "2") (pinfunction "2_2") (pintype "passive"))
    )
    (net (code "52") (name "/DDS_CLKB_N0") (class "Default")
      (node (ref "C66") (pin "1") (pinfunction "1_1") (pintype "passive"))
    )
    (net (code "53") (name "/DDS_CLKB_N1") (class "Default")
      (node (ref "C61") (pin "1") (pinfunction "1_1") (pintype "passive"))
    )
    (net (code "54") (name "/DDS_CLKB_N2") (class "Default")
      (node (ref "C71") (pin "1") (pinfunction "1_1") (pintype "passive"))
    )
    (net (code "55") (name "/DDS_CLKB_N3") (class "Default")
      (node (ref "C96") (pin "1") (pinfunction "1_1") (pintype "passive"))
    )
    (net (code "57") (name "/DDS_CLKB_P0") (class "Default")
      (node (ref "C65") (pin "1") (pinfunction "1_1") (pintype "passive"))
    )
    (net (code "58") (name "/DDS_CLKB_P1") (class "Default")
      (node (ref "C56") (pin "1") (pinfunction "1_1") (pintype "passive"))
    )
    (net (code "59") (name "/DDS_CLKB_P2") (class "Default")
      (node (ref "C68") (pin "1") (pinfunction "1_1") (pintype "passive"))
    )
    (net (code "60") (name "/DDS_CLKB_P3") (class "Default")
      (node (ref "C95") (pin "1") (pinfunction "1_1") (pintype "passive"))
    )
    (net (code "62") (name "/IN_SEL") (class "Default")
      (node (ref "R154") (pin "1") (pinfunction "1_1") (pintype "passive"))
    )
    (net (code "63") (name "/MMCX_OSCn_SEL") (class "Default")
      (node (ref "R165") (pin "1") (pinfunction "1_1") (pintype "passive"))
    )
    (net (code "64") (name "/OSC_ENn") (class "Default")
      (node (ref "T1") (pin "1") (pinfunction "G_1") (pintype "passive"))
    )
    (net (code "66") (name "GND") (class "Default")
      (node (ref "C100") (pin "1") (pinfunction "1_1") (pintype "passive"))
      (node (ref "C101") (pin "1") (pinfunction "1_1") (pintype "passive"))
      (node (ref "C102") (pin "1") (pinfunction "1_1") (pintype "passive"))
      (node (ref "C121") (pin "1") (pinfunction "1_1") (pintype "passive"))
      (node (ref "C122") (pin "2") (pinfunction "2_2") (pintype "passive"))
      (node (ref "C123") (pin "1") (pinfunction "1_1") (pintype "passive"))
      (node (ref "C131") (pin "1") (pinfunction "1_1") (pintype "passive"))
      (node (ref "C145") (pin "1") (pinfunction "1_1") (pintype "passive"))
      (node (ref "C191") (pin "1") (pinfunction "1_1") (pintype "passive"))
      (node (ref "C195") (pin "2") (pinfunction "2_2") (pintype "passive"))
      (node (ref "C212") (pin "2") (pinfunction "2_2") (pintype "passive"))
      (node (ref "C224") (pin "1") (pinfunction "1_1") (pintype "passive"))
      (node (ref "C69") (pin "1") (pinfunction "1_1") (pintype "passive"))
      (node (ref "C80") (pin "2") (pinfunction "2_2") (pintype "passive"))
      (node (ref "C91") (pin "1") (pinfunction "1_1") (pintype "passive"))
      (node (ref "C94") (pin "1") (pinfunction "1_1") (pintype "passive"))
      (node (ref "C97") (pin "1") (pinfunction "1_1") (pintype "passive"))
      (node (ref "C98") (pin "1") (pinfunction "1_1") (pintype "passive"))
      (node (ref "IC19") (pin "22") (pinfunction "GND_22") (pintype "power_in"))
      (node (ref "IC19") (pin "39") (pinfunction "GND_39") (pintype "power_in"))
      (node (ref "IC19") (pin "45") (pinfunction "GND_45") (pintype "power_in"))
      (node (ref "IC19") (pin "6") (pinfunction "GND_6") (pintype "power_in"))
      (node (ref "IC24") (pin "1") (pinfunction "GND_1") (pintype "power_in"))
      (node (ref "IC24") (pin "17") (pinfunction "GND_17") (pintype "power_in"))
      (node (ref "IC25") (pin "2") (pinfunction "V-_2") (pintype "power_in"))
      (node (ref "J10") (pin "1") (pinfunction "1_1") (pintype "bidirectional"))
      (node (ref "J10") (pin "13") (pinfunction "13_13") (pintype "bidirectional"))
      (node (ref "J10") (pin "14") (pinfunction "14_14") (pintype "bidirectional"))
      (node (ref "J10") (pin "19") (pinfunction "19_19") (pintype "bidirectional"))
      (node (ref "J10") (pin "2") (pinfunction "2_2") (pintype "bidirectional"))
      (node (ref "J10") (pin "20") (pinfunction "20_20") (pintype "bidirectional"))
      (node (ref "J10") (pin "7") (pinfunction "7_7") (pintype "bidirectional"))
      (node (ref "J10") (pin "8") (pinfunction "8_8") (pintype "bidirectional"))
      (node (ref "J7") (pin "2") (pinfunction "2_2") (pintype "bidirectional"))
      (node (ref "OSC1") (pin "2") (pinfunction "GND_2") (pintype "power_in"))
      (node (ref "OSC2") (pin "2") (pinfunction "GND_2") (pintype "passive"))
      (node (ref "R101") (pin "1") (pinfunction "1_1") (pintype "passive"))
      (node (ref "R102") (pin "1") (pinfunction "1_1") (pintype "passive"))
      (node (ref "R108") (pin "2") (pinfunction "2_2") (pintype "passive"))
      (node (ref "R110") (pin "2") (pinfunction "2_2") (pintype "passive"))
      (node (ref "R141") (pin "1") (pinfunction "1_1") (pintype "passive"))
      (node (ref "R168") (pin "1") (pinfunction "1_1") (pintype "passive"))
      (node (ref "R189") (pin "1") (pinfunction "1_1") (pintype "passive"))
      (node (ref "R190") (pin "2") (pinfunction "2_2") (pintype "passive"))
      (node (ref "R24") (pin "2") (pinfunction "2_2") (pintype "passive"))
      (node (ref "R34") (pin "1") (pinfunction "1_1") (pintype "passive"))
      (node (ref "R37") (pin "1") (pinfunction "1_1") (pintype "passive"))
      (node (ref "R42") (pin "1") (pinfunction "1_1") (pintype "passive"))
      (node (ref "R45") (pin "1") (pinfunction "1_1") (pintype "passive"))
      (node (ref "R60") (pin "1") (pinfunction "1_1") (pintype "passive"))
      (node (ref "R61") (pin "1") (pinfunction "1_1") (pintype "passive"))
      (node (ref "R62") (pin "1") (pinfunction "1_1") (pintype "passive"))
      (node (ref "R63") (pin "1") (pinfunction "1_1") (pintype "passive"))
      (node (ref "R69") (pin "1") (pinfunction "1_1") (pintype "passive"))
      (node (ref "R70") (pin "1") (pinfunction "1_1") (pintype "passive"))
      (node (ref "R71") (pin "1") (pinfunction "1_1") (pintype "passive"))
      (node (ref "R72") (pin "1") (pinfunction "1_1") (pintype "passive"))
      (node (ref "R76") (pin "1") (pinfunction "1_1") (pintype "passive"))
      (node (ref "R77") (pin "1") (pinfunction "1_1") (pintype "passive"))
      (node (ref "R81") (pin "1") (pinfunction "1_1") (pintype "passive"))
      (node (ref "R95") (pin "1") (pinfunction "1_1") (pintype "passive"))
      (node (ref "TR2") (pin "1") (pinfunction "P1_1") (pintype "passive"))
      (node (ref "TR2") (pin "2") (pinfunction "P1_2") (pintype "passive"))
      (node (ref "TR2") (pin "5") (pinfunction "NC_5") (pintype "passive"))
      (node (ref "TR3") (pin "1") (pinfunction "P1_1") (pintype "passive"))
      (node (ref "TR3") (pin "2") (pinfunction "P1_2") (pintype "passive"))
      (node (ref "TR3") (pin "5") (pinfunction "NC_5") (pintype "passive"))
      (node (ref "TR9") (pin "5") (pinfunction "NC_5") (pintype "passive"))
    )
    (net (code "67") (name "Net-(C103-Pad2)") (class "Default")
      (node (ref "C103") (pin "2") (pinfunction "2_2") (pintype "passive"))
      (node (ref "R117") (pin "1") (pinfunction "1_1") (pintype "passive"))
    )
    (net (code "68") (name "Net-(C121-Pad2)") (class "Default")
      (node (ref "C121") (pin "2") (pinfunction "2_2") (pintype "passive"))
      (node (ref "C224") (pin "2") (pinfunction "2_2") (pintype "passive"))
      (node (ref "R16") (pin "2") (pinfunction "2_2") (pintype "passive"))
      (node (ref "R24") (pin "1") (pinfunction "1_1") (pintype "passive"))
      (node (ref "TR9") (pin "1") (pinfunction "P1_1") (pintype "passive"))
      (node (ref "TR9") (pin "2") (pinfunction "P1_2") (pintype "passive"))
    )
    (net (code "69") (name "Net-(C190-Pad1)") (class "Default")
      (node (ref "C190") (pin "1") (pinfunction "1_1") (pintype "passive"))
      (node (ref "J7") (pin "1") (pinfunction "1_1") (pintype "bidirectional"))
    )
    (net (code "70") (name "Net-(C190-Pad2)") (class "Default")
      (node (ref "C190") (pin "2") (pinfunction "2_2") (pintype "passive"))
      (node (ref "R73") (pin "1") (pinfunction "1_1") (pintype "passive"))
      (node (ref "TR3") (pin "3") (pinfunction "P1_3") (pintype "passive"))
    )
    (net (code "71") (name "Net-(C196-Pad2)") (class "Default")
      (node (ref "C196") (pin "2") (pinfunction "2_2") (pintype "passive"))
      (node (ref "R46") (pin "1") (pinfunction "1_1") (pintype "passive"))
      (node (ref "TR2") (pin "3") (pinfunction "P1_3") (pintype "passive"))
    )
    (net (code "72") (name "Net-(IC19-CLK_SEL)") (class "Default")
      (node (ref "IC19") (pin "23") (pinfunction "CLK_SEL_23") (pintype "input"))
      (node (ref "R154") (pin "2") (pinfunction "2_2") (pintype "passive"))
    )
    (net (code "73") (name "Net-(IC19-DIVA)") (class "Default")
      (node (ref "IC19") (pin "1") (pinfunction "DIVA_1") (pintype "input"))
      (node (ref "IC19") (pin "33") (pinfunction "DIVB_33") (pintype "input"))
      (node (ref "R155") (pin "2") (pinfunction "2_2") (pintype "passive"))
    )
    (net (code "74") (name "Net-(IC19-OEA)") (class "Default")
      (node (ref "IC19") (pin "16") (pinfunction "OEA_16") (pintype "input"))
      (node (ref "R103") (pin "2") (pinfunction "2_2") (pintype "passive"))
      (node (ref "R108") (pin "1") (pinfunction "1_1") (pintype "passive"))
    )
    (net (code "75") (name "Net-(IC19-OEB)") (class "Default")
      (node (ref "IC19") (pin "18") (pinfunction "OEB_18") (pintype "input"))
      (node (ref "R109") (pin "2") (pinfunction "2_2") (pintype "passive"))
      (node (ref "R110") (pin "1") (pinfunction "1_1") (pintype "passive"))
    )
    (net (code "76") (name "Net-(IC19-SFOUTA0)") (class "Default")
      (node (ref "IC19") (pin "2") (pinfunction "SFOUTA1_2") (pintype "input"))
      (node (ref "IC19") (pin "3") (pinfunction "SFOUTA0_3") (pintype "input"))
      (node (ref "IC19") (pin "31") (pinfunction "SFOUTB0_31") (pintype "input"))
      (node (ref "IC19") (pin "32") (pinfunction "SFOUTB1_32") (pintype "input"))
      (node (ref "R141") (pin "2") (pinfunction "2_2") (pintype "passive"))
    )
    (net (code "77") (name "Net-(IC19-VDD)") (class "Default")
      (node (ref "C100") (pin "2") (pinfunction "2_2") (pintype "passive"))
      (node (ref "C91") (pin "2") (pinfunction "2_2") (pintype "passive"))
      (node (ref "C97") (pin "2") (pinfunction "2_2") (pintype "passive"))
      (node (ref "C98") (pin "2") (pinfunction "2_2") (pintype "passive"))
      (node (ref "IC19") (pin "12") (pinfunction "VDD_12") (pintype "power_in"))
      (node (ref "IC19") (pin "34") (pinfunction "VDDOB_34") (pintype "power_in"))
      (node (ref "IC19") (pin "44") (pinfunction "VDDOA_44") (pintype "power_in"))
      (node (ref "L14") (pin "1") (pinfunction "1_1") (pintype "passive"))
      (node (ref "R103") (pin "1") (pinfunction "1_1") (pintype "passive"))
      (node (ref "R109") (pin "1") (pinfunction "1_1") (pintype "passive"))
      (node (ref "R151") (pin "2") (pinfunction "2_2") (pintype "passive"))
    )
    (net (code "78") (name "Net-(IC19-VREF)") (class "Default")
      (node (ref "C94") (pin "2") (pinfunction "2_2") (pintype "passive"))
      (node (ref "IC19") (pin "17") (pinfunction "VREF_17") (pintype "output"))
    )
    (net (code "79") (name "Net-(IC24-CLK_SEL)") (class "Default")
      (node (ref "IC24") (pin "2") (pinfunction "CLK_SEL_2") (pintype "input"))
      (node (ref "R165") (pin "2") (pinfunction "2_2") (pintype "passive"))
    )
    (net (code "80") (name "Net-(IC24-VDD)") (class "Default")
      (node (ref "C123") (pin "2") (pinfunction "2_2") (pintype "passive"))
      (node (ref "C131") (pin "2") (pinfunction "2_2") (pintype "passive"))
      (node (ref "IC24") (pin "5") (pinfunction "VDD_5") (pintype "power_in"))
      (node (ref "L10") (pin "1") (pinfunction "1_1") (pintype "passive"))
      (node (ref "R164") (pin "2") (pinfunction "2_2") (pintype "passive"))
    )
    (net (code "81") (name "Net-(IC24-~{CLK0})") (class "Default")
      (node (ref "C122") (pin "1") (pinfunction "1_1") (pintype "passive"))
      (node (ref "IC24") (pin "7") (pinfunction "~{CLK0}_7") (pintype "input"))
      (node (ref "R162") (pin "2") (pinfunction "2_2") (pintype "passive"))
    )
    (net (code "82") (name "Net-(IC25-IN+)") (class "Default")
      (node (ref "IC25") (pin "1") (pinfunction "IN+_1") (pintype "input"))
      (node (ref "R186") (pin "1") (pinfunction "1_1") (pintype "passive"))
      (node (ref "R188") (pin "2") (pinfunction "2_2") (pintype "passive"))
      (node (ref "R189") (pin "2") (pinfunction "2_2") (pintype "passive"))
    )
    (net (code "83") (name "Net-(IC25-IN-)") (class "Default")
      (node (ref "IC25") (pin "3") (pinfunction "IN-_3") (pintype "input"))
      (node (ref "R183") (pin "1") (pinfunction "1_1") (pintype "passive"))
      (node (ref "R184") (pin "1") (pinfunction "1_1") (pintype "passive"))
      (node (ref "R185") (pin "1") (pinfunction "1_1") (pintype "passive"))
    )
    (net (code "84") (name "Net-(IC25-OUT)") (class "Default")
      (node (ref "IC25") (pin "4") (pinfunction "OUT_4") (pintype "output"))
      (node (ref "R183") (pin "2") (pinfunction "2_2") (pintype "passive"))
      (node (ref "R184") (pin "2") (pinfunction "2_2") (pintype "passive"))
      (node (ref "R187") (pin "1") (pinfunction "1_1") (pintype "passive"))
    )
    (net (code "85") (name "Net-(IC25-V+)") (class "Default")
      (node (ref "C101") (pin "2") (pinfunction "2_2") (pintype "passive"))
      (node (ref "C102") (pin "2") (pinfunction "2_2") (pintype "passive"))
      (node (ref "C212") (pin "1") (pinfunction "1_1") (pintype "passive"))
      (node (ref "IC25") (pin "5") (pinfunction "V+_5") (pintype "power_in"))
      (node (ref "L9") (pin "1") (pinfunction "1_1") (pintype "passive"))
      (node (ref "OSC1") (pin "4") (pinfunction "VDD_4") (pintype "power_in"))
      (node (ref "OSC2") (pin "1") (pinfunction "OE_1") (pintype "passive"))
      (node (ref "OSC2") (pin "4") (pinfunction "VDD_4") (pintype "passive"))
      (node (ref "R167") (pin "2") (pinfunction "2_2") (pintype "passive"))
      (node (ref "R188") (pin "1") (pinfunction "1_1") (pintype "passive"))
    )
    (net (code "86") (name "Net-(J9-Pad1)") (class "Default")
      (node (ref "J9") (pin "1") (pinfunction "1_1") (pintype "bidirectional"))
      (node (ref "R186") (pin "2") (pinfunction "2_2") (pintype "passive"))
      (node (ref "R191") (pin "1") (pinfunction "1_1") (pintype "passive"))
    )
    (net (code "87") (name "Net-(J9-Pad2)") (class "Default")
      (node (ref "J9") (pin "2") (pinfunction "2_2") (pintype "bidirectional"))
      (node (ref "R185") (pin "2") (pinfunction "2_2") (pintype "passive"))
      (node (ref "R190") (pin "1") (pinfunction "1_1") (pintype "passive"))
    )
    (net (code "88") (name "Net-(OSC1-NC)") (class "Default")
      (node (ref "C145") (pin "2") (pinfunction "2_2") (pintype "passive"))
      (node (ref "OSC1") (pin "1") (pinfunction "NC_1") (pintype "passive"))
      (node (ref "R167") (pin "1") (pinfunction "1_1") (pintype "passive"))
      (node (ref "R168") (pin "2") (pinfunction "2_2") (pintype "passive"))
      (node (ref "R187") (pin "2") (pinfunction "2_2") (pintype "passive"))
      (node (ref "R191") (pin "2") (pinfunction "2_2") (pintype "passive"))
    )
    (net (code "89") (name "Net-(OSC1-OUT)") (class "Default")
      (node (ref "OSC1") (pin "3") (pinfunction "OUT_3") (pintype "output"))
      (node (ref "OSC2") (pin "3") (pinfunction "CLK_3") (pintype "passive"))
      (node (ref "R117") (pin "2") (pinfunction "2_2") (pintype "passive"))
    )
    (net (code "90") (name "Net-(T1-D)") (class "Default")
      (node (ref "L9") (pin "2") (pinfunction "2_2") (pintype "passive"))
      (node (ref "T1") (pin "3") (pinfunction "D_3") (pintype "passive"))
    )
    (net (code "91") (name "P1V8A") (class "Default")
      (node (ref "R151") (pin "1") (pinfunction "1_1") (pintype "passive"))
      (node (ref "R164") (pin "1") (pinfunction "1_1") (pintype "passive"))
    )
    (net (code "92") (name "P3V3A") (class "Default")
      (node (ref "L10") (pin "2") (pinfunction "2_2") (pintype "passive"))
      (node (ref "L14") (pin "2") (pinfunction "2_2") (pintype "passive"))
      (node (ref "R16") (pin "1") (pinfunction "1_1") (pintype "passive"))
      (node (ref "T1") (pin "2") (pinfunction "S_2") (pintype "passive"))
    )
    (net (code "93") (name "unconnected-(IC19-NC-Pad11)") (class "Default")
      (node (ref "IC19") (pin "11") (pinfunction "NC_11") (pintype "passive+no_connect"))
    )
    (net (code "94") (name "unconnected-(IC19-NC-Pad13)") (class "Default")
      (node (ref "IC19") (pin "13") (pinfunction "NC_13") (pintype "passive+no_connect"))
    )
    (net (code "95") (name "unconnected-(IC19-NC-Pad21)") (class "Default")
      (node (ref "IC19") (pin "21") (pinfunction "NC_21") (pintype "passive+no_connect"))
    )
    (net (code "96") (name "unconnected-(IC19-NC-Pad28)") (class "Default")
      (node (ref "IC19") (pin "28") (pinfunction "NC_28") (pintype "passive+no_connect"))
    )
    (net (code "97") (name "unconnected-(IC19-Q4-Pad41)") (class "Default")
      (node (ref "IC19") (pin "41") (pinfunction "Q4_41") (pintype "output+no_connect"))
    )
    (net (code "98") (name "unconnected-(IC19-Q9-Pad25)") (class "Default")
      (node (ref "IC19") (pin "25") (pinfunction "Q9_25") (pintype "output+no_connect"))
    )
    (net (code "99") (name "unconnected-(IC19-~{Q4}-Pad40)") (class "Default")
      (node (ref "IC19") (pin "40") (pinfunction "~{Q4}_40") (pintype "output+no_connect"))
    )
    (net (code "100") (name "unconnected-(IC19-~{Q9}-Pad24)") (class "Default")
      (node (ref "IC19") (pin "24") (pinfunction "~{Q9}_24") (pintype "output+no_connect"))
    )
    (net (code "101") (name "unconnected-(IC24-Q1-Pad11)") (class "Default")
      (node (ref "IC24") (pin "11") (pinfunction "Q1_11") (pintype "output+no_connect"))
    )
    (net (code "102") (name "unconnected-(IC24-Q2-Pad13)") (class "Default")
      (node (ref "IC24") (pin "13") (pinfunction "Q2_13") (pintype "output+no_connect"))
    )
    (net (code "103") (name "unconnected-(IC24-~{Q1}-Pad12)") (class "Default")
      (node (ref "IC24") (pin "12") (pinfunction "~{Q1}_12") (pintype "output+no_connect"))
    )
    (net (code "104") (name "unconnected-(IC24-~{Q2}-Pad14)") (class "Default")
      (node (ref "IC24") (pin "14") (pinfunction "~{Q2}_14") (pintype "output+no_connect"))
    )
    (net (code "105") (name "unconnected-(J10-Pad3)") (class "Default")
      (node (ref "J10") (pin "3") (pinfunction "3_3") (pintype "bidirectional"))
    )
    (net (code "106") (name "unconnected-(J10-Pad4)") (class "Default")
      (node (ref "J10") (pin "4") (pinfunction "4_4") (pintype "bidirectional"))
    )
    (net (code "107") (name "unconnected-(J10-Pad5)") (class "Default")
      (node (ref "J10") (pin "5") (pinfunction "5_5") (pintype "bidirectional"))
    )
    (net (code "108") (name "unconnected-(J10-Pad6)") (class "Default")
      (node (ref "J10") (pin "6") (pinfunction "6_6") (pintype "bidirectional"))
    )
    (net (code "109") (name "unconnected-(J10-Pad9)") (class "Default")
      (node (ref "J10") (pin "9") (pinfunction "9_9") (pintype "bidirectional"))
    )
    (net (code "110") (name "unconnected-(J10-Pad10)") (class "Default")
      (node (ref "J10") (pin "10") (pinfunction "10_10") (pintype "bidirectional"))
    )
    (net (code "111") (name "unconnected-(J10-Pad11)") (class "Default")
      (node (ref "J10") (pin "11") (pinfunction "11_11") (pintype "bidirectional"))
    )
    (net (code "112") (name "unconnected-(J10-Pad12)") (class "Default")
      (node (ref "J10") (pin "12") (pinfunction "12_12") (pintype "bidirectional"))
    )
    (net (code "113") (name "unconnected-(J10-Pad16)") (class "Default")
      (node (ref "J10") (pin "16") (pinfunction "16_16") (pintype "bidirectional"))
    )
    (net (code "114") (name "unconnected-(J10-Pad18)") (class "Default")
      (node (ref "J10") (pin "18") (pinfunction "18_18") (pintype "bidirectional"))
    )
  )
)
